# THB6064.net
KiCad netlist of a schematic drawn in EAGLE
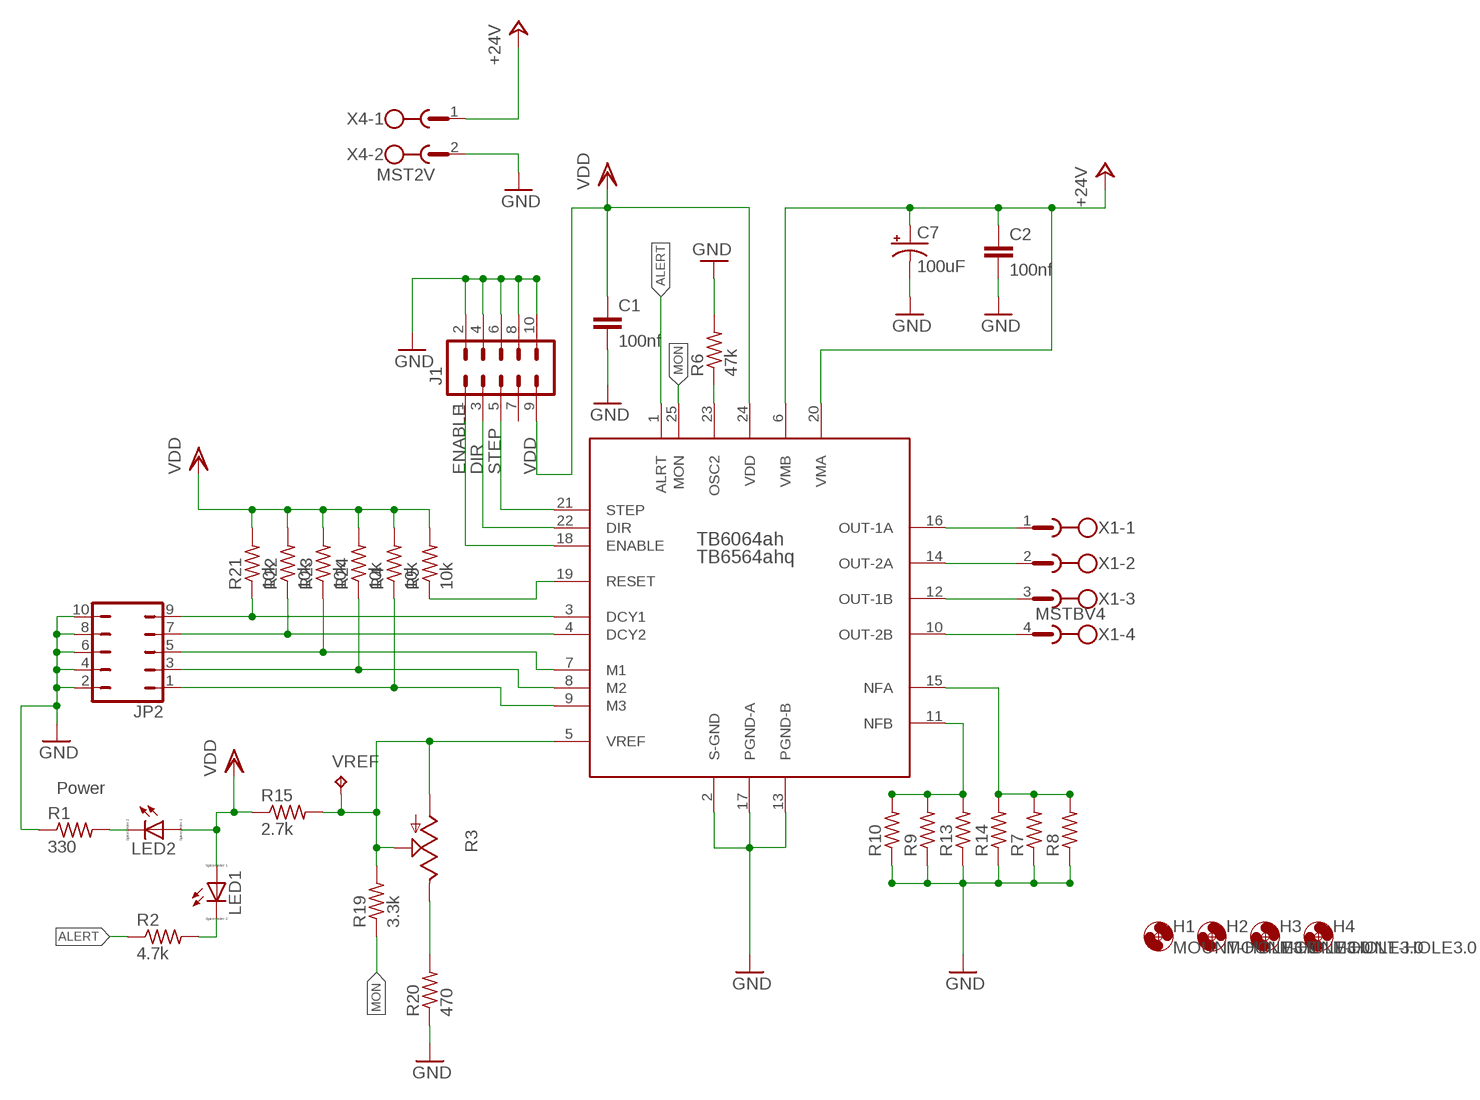
[diagram p0: schematic, sheet 1]

(export (version "E")
  (design (tool "Eeschema 10.0.6"))
  (components
    (comp (ref "C1")
      (value "100nf")
      (footprint "eagle-import:C1206")
      (libsource (lib "eagle-import") (part "C-EUC1206"))
    )
    (comp (ref "C2")
      (value "100nf")
      (footprint "eagle-import:C1206")
      (libsource (lib "eagle-import") (part "C-EUC1206"))
    )
    (comp (ref "C7")
      (value "100uF")
      (footprint "eagle-import:NIC_10X10.5_CAP")
      (libsource (lib "eagle-import") (part "100UF-63V-20%(ELECT)"))
    )
    (comp (ref "H1")
      (value "MOUNT-HOLE3.0")
      (footprint "eagle-import:3,0")
      (libsource (lib "eagle-import") (part "MOUNT-HOLE3.0"))
    )
    (comp (ref "H2")
      (value "MOUNT-HOLE3.0")
      (footprint "eagle-import:3,0")
      (libsource (lib "eagle-import") (part "MOUNT-HOLE3.0"))
    )
    (comp (ref "H3")
      (value "MOUNT-HOLE3.0")
      (footprint "eagle-import:3,0")
      (libsource (lib "eagle-import") (part "MOUNT-HOLE3.0"))
    )
    (comp (ref "H4")
      (value "MOUNT-HOLE3.0")
      (footprint "eagle-import:3,0")
      (libsource (lib "eagle-import") (part "MOUNT-HOLE3.0"))
    )
    (comp (ref "J1")
      (value "M05X2SHD")
      (footprint "eagle-import:2X5-SHROUDED")
      (libsource (lib "eagle-import") (part "M05X2SHD"))
    )
    (comp (ref "JP2")
      (value "JP5Q")
      (footprint "eagle-import:JP5Q")
      (libsource (lib "eagle-import") (part "JP5Q"))
    )
    (comp (ref "LED1")
      (value "LED_E")
      (footprint "eagle-import:LED_1206")
      (libsource (lib "eagle-import") (part "LED_E"))
    )
    (comp (ref "LED2")
      (value "LED_E")
      (footprint "eagle-import:LED_1206")
      (libsource (lib "eagle-import") (part "LED_E"))
    )
    (comp (ref "R1")
      (value "330")
      (footprint "eagle-import:R1206")
      (libsource (lib "eagle-import") (part "R-US_R1206"))
    )
    (comp (ref "R2")
      (value "4.7k")
      (footprint "eagle-import:R1206")
      (libsource (lib "eagle-import") (part "R-US_R1206"))
    )
    (comp (ref "R3")
      (value "TRIM_US-CA6V")
      (footprint "eagle-import:CA6V")
      (libsource (lib "eagle-import") (part "TRIM_US-CA6V"))
    )
    (comp (ref "R4")
      (value "10k")
      (footprint "eagle-import:R1206")
      (libsource (lib "eagle-import") (part "R-US_R1206"))
    )
    (comp (ref "R5")
      (value "10k")
      (footprint "eagle-import:R1206")
      (libsource (lib "eagle-import") (part "R-US_R1206"))
    )
    (comp (ref "R6")
      (value "47k")
      (footprint "eagle-import:R1206")
      (libsource (lib "eagle-import") (part "R-US_R1206"))
    )
    (comp (ref "R7")
      (value "R-US_R2512")
      (footprint "eagle-import:R2512")
      (libsource (lib "eagle-import") (part "R-US_R2512"))
    )
    (comp (ref "R8")
      (value "R-US_R2512")
      (footprint "eagle-import:R2512")
      (libsource (lib "eagle-import") (part "R-US_R2512"))
    )
    (comp (ref "R9")
      (value "R-US_R2512")
      (footprint "eagle-import:R2512")
      (libsource (lib "eagle-import") (part "R-US_R2512"))
    )
    (comp (ref "R10")
      (value "R-US_R2512")
      (footprint "eagle-import:R2512")
      (libsource (lib "eagle-import") (part "R-US_R2512"))
    )
    (comp (ref "R13")
      (value "R-US_R2512")
      (footprint "eagle-import:R2512")
      (libsource (lib "eagle-import") (part "R-US_R2512"))
    )
    (comp (ref "R14")
      (value "R-US_R2512")
      (footprint "eagle-import:R2512")
      (libsource (lib "eagle-import") (part "R-US_R2512"))
    )
    (comp (ref "R15")
      (value "2.7k")
      (footprint "eagle-import:R1206")
      (libsource (lib "eagle-import") (part "R-US_R1206"))
    )
    (comp (ref "R19")
      (value "3.3k")
      (footprint "eagle-import:R1206")
      (libsource (lib "eagle-import") (part "R-US_R1206"))
    )
    (comp (ref "R20")
      (value "470")
      (footprint "eagle-import:R1206")
      (libsource (lib "eagle-import") (part "R-US_R1206"))
    )
    (comp (ref "R21")
      (value "10k")
      (footprint "eagle-import:R1206")
      (libsource (lib "eagle-import") (part "R-US_R1206"))
    )
    (comp (ref "R22")
      (value "10k")
      (footprint "eagle-import:R1206")
      (libsource (lib "eagle-import") (part "R-US_R1206"))
    )
    (comp (ref "R23")
      (value "10k")
      (footprint "eagle-import:R1206")
      (libsource (lib "eagle-import") (part "R-US_R1206"))
    )
    (comp (ref "R24")
      (value "10k")
      (footprint "eagle-import:R1206")
      (libsource (lib "eagle-import") (part "R-US_R1206"))
    )
    (comp (ref "U$1")
      (value "THB6064")
      (footprint "eagle-import:ZIP25")
      (libsource (lib "eagle-import") (part "THB6064"))
    )
    (comp (ref "VREF")
      (value "TPPAD1-17")
      (footprint "eagle-import:P1-17")
      (libsource (lib "eagle-import") (part "TPPAD1-17"))
    )
    (comp (ref "X1")
      (value "MSTBV4")
      (footprint "eagle-import:MSTBV4")
      (fields (field (name "MPN") "MSTBV 2,5/4-GF-5.08"))
      (libsource (lib "eagle-import") (part "MSTBV4"))
    )
    (comp (ref "X4")
      (value "MST2V")
      (footprint "eagle-import:MSTBV2")
      (libsource (lib "eagle-import") (part "MST2V"))
    )
  )
  (nets
    (net (code "1") (name "+24V") (class "Default")
      (node (ref "C2") (pin "1") (pinfunction "1_1") (pintype "passive"))
      (node (ref "C7") (pin "+") (pinfunction "+_+") (pintype "passive"))
      (node (ref "U$1") (pin "20") (pinfunction "VMA_20") (pintype "bidirectional"))
      (node (ref "U$1") (pin "6") (pinfunction "VMB_6") (pintype "bidirectional"))
      (node (ref "X4") (pin "1") (pinfunction "1_1") (pintype "passive"))
    )
    (net (code "2") (name "/DIR") (class "Default")
      (node (ref "J1") (pin "3") (pinfunction "3_3") (pintype "passive"))
      (node (ref "U$1") (pin "22") (pinfunction "DIR_22") (pintype "bidirectional"))
    )
    (net (code "3") (name "/ENABLE") (class "Default")
      (node (ref "J1") (pin "1") (pinfunction "1_1") (pintype "passive"))
      (node (ref "U$1") (pin "18") (pinfunction "ENABLE_18") (pintype "bidirectional"))
    )
    (net (code "4") (name "/STEP") (class "Default")
      (node (ref "J1") (pin "5") (pinfunction "5_5") (pintype "passive"))
      (node (ref "U$1") (pin "21") (pinfunction "STEP_21") (pintype "bidirectional"))
    )
    (net (code "5") (name "ALERT") (class "Default")
      (node (ref "R2") (pin "1") (pinfunction "1_1") (pintype "passive"))
      (node (ref "U$1") (pin "1") (pinfunction "ALRT_1") (pintype "bidirectional"))
    )
    (net (code "6") (name "GND") (class "Default")
      (node (ref "C1") (pin "2") (pinfunction "2_2") (pintype "passive"))
      (node (ref "C2") (pin "2") (pinfunction "2_2") (pintype "passive"))
      (node (ref "C7") (pin "-") (pinfunction "-_-") (pintype "passive"))
      (node (ref "J1") (pin "10") (pinfunction "10_10") (pintype "passive"))
      (node (ref "J1") (pin "2") (pinfunction "2_2") (pintype "passive"))
      (node (ref "J1") (pin "4") (pinfunction "4_4") (pintype "passive"))
      (node (ref "J1") (pin "6") (pinfunction "6_6") (pintype "passive"))
      (node (ref "J1") (pin "8") (pinfunction "8_8") (pintype "passive"))
      (node (ref "JP2") (pin "10") (pinfunction "10_10") (pintype "passive"))
      (node (ref "JP2") (pin "2") (pinfunction "2_2") (pintype "passive"))
      (node (ref "JP2") (pin "4") (pinfunction "4_4") (pintype "passive"))
      (node (ref "JP2") (pin "6") (pinfunction "6_6") (pintype "passive"))
      (node (ref "JP2") (pin "8") (pinfunction "8_8") (pintype "passive"))
      (node (ref "R1") (pin "1") (pinfunction "1_1") (pintype "passive"))
      (node (ref "R10") (pin "1") (pinfunction "1_1") (pintype "passive"))
      (node (ref "R13") (pin "1") (pinfunction "1_1") (pintype "passive"))
      (node (ref "R14") (pin "1") (pinfunction "1_1") (pintype "passive"))
      (node (ref "R20") (pin "1") (pinfunction "1_1") (pintype "passive"))
      (node (ref "R6") (pin "2") (pinfunction "2_2") (pintype "passive"))
      (node (ref "R7") (pin "1") (pinfunction "1_1") (pintype "passive"))
      (node (ref "R8") (pin "1") (pinfunction "1_1") (pintype "passive"))
      (node (ref "R9") (pin "1") (pinfunction "1_1") (pintype "passive"))
      (node (ref "U$1") (pin "13") (pinfunction "PGND-B_13") (pintype "bidirectional"))
      (node (ref "U$1") (pin "17") (pinfunction "PGND-A_17") (pintype "bidirectional"))
      (node (ref "U$1") (pin "2") (pinfunction "S-GND_2") (pintype "bidirectional"))
      (node (ref "X4") (pin "2") (pinfunction "1_2") (pintype "passive"))
    )
    (net (code "7") (name "MON") (class "Default")
      (node (ref "R19") (pin "1") (pinfunction "1_1") (pintype "passive"))
      (node (ref "U$1") (pin "25") (pinfunction "MON_25") (pintype "bidirectional"))
    )
    (net (code "8") (name "Net-(LED1-PadC)") (class "Default")
      (node (ref "LED1") (pin "C") (pinfunction "C_C") (pintype "passive"))
      (node (ref "R2") (pin "2") (pinfunction "2_2") (pintype "passive"))
    )
    (net (code "9") (name "Net-(LED2-PadC)") (class "Default")
      (node (ref "LED2") (pin "C") (pinfunction "C_C") (pintype "passive"))
      (node (ref "R1") (pin "2") (pinfunction "2_2") (pintype "passive"))
    )
    (net (code "10") (name "Net-(R20-Pad2)") (class "Default")
      (node (ref "R20") (pin "2") (pinfunction "2_2") (pintype "passive"))
      (node (ref "R3") (pin "E") (pinfunction "E_E") (pintype "passive"))
    )
    (net (code "11") (name "Net-(U$1-DCY1)") (class "Default")
      (node (ref "JP2") (pin "9") (pinfunction "9_9") (pintype "passive"))
      (node (ref "R21") (pin "1") (pinfunction "1_1") (pintype "passive"))
      (node (ref "U$1") (pin "3") (pinfunction "DCY1_3") (pintype "bidirectional"))
    )
    (net (code "12") (name "Net-(U$1-DCY2)") (class "Default")
      (node (ref "JP2") (pin "7") (pinfunction "7_7") (pintype "passive"))
      (node (ref "R22") (pin "1") (pinfunction "1_1") (pintype "passive"))
      (node (ref "U$1") (pin "4") (pinfunction "DCY2_4") (pintype "bidirectional"))
    )
    (net (code "13") (name "Net-(U$1-M1)") (class "Default")
      (node (ref "JP2") (pin "5") (pinfunction "5_5") (pintype "passive"))
      (node (ref "R23") (pin "1") (pinfunction "1_1") (pintype "passive"))
      (node (ref "U$1") (pin "7") (pinfunction "M1_7") (pintype "bidirectional"))
    )
    (net (code "14") (name "Net-(U$1-M2)") (class "Default")
      (node (ref "JP2") (pin "3") (pinfunction "3_3") (pintype "passive"))
      (node (ref "R24") (pin "1") (pinfunction "1_1") (pintype "passive"))
      (node (ref "U$1") (pin "8") (pinfunction "M2_8") (pintype "bidirectional"))
    )
    (net (code "15") (name "Net-(U$1-M3)") (class "Default")
      (node (ref "JP2") (pin "1") (pinfunction "1_1") (pintype "passive"))
      (node (ref "R4") (pin "1") (pinfunction "1_1") (pintype "passive"))
      (node (ref "U$1") (pin "9") (pinfunction "M3_9") (pintype "bidirectional"))
    )
    (net (code "16") (name "Net-(U$1-NFA)") (class "Default")
      (node (ref "R14") (pin "2") (pinfunction "2_2") (pintype "passive"))
      (node (ref "R7") (pin "2") (pinfunction "2_2") (pintype "passive"))
      (node (ref "R8") (pin "2") (pinfunction "2_2") (pintype "passive"))
      (node (ref "U$1") (pin "15") (pinfunction "NFA_15") (pintype "bidirectional"))
    )
    (net (code "17") (name "Net-(U$1-NFB)") (class "Default")
      (node (ref "R10") (pin "2") (pinfunction "2_2") (pintype "passive"))
      (node (ref "R13") (pin "2") (pinfunction "2_2") (pintype "passive"))
      (node (ref "R9") (pin "2") (pinfunction "2_2") (pintype "passive"))
      (node (ref "U$1") (pin "11") (pinfunction "NFB_11") (pintype "bidirectional"))
    )
    (net (code "18") (name "Net-(U$1-OSC2)") (class "Default")
      (node (ref "R6") (pin "1") (pinfunction "1_1") (pintype "passive"))
      (node (ref "U$1") (pin "23") (pinfunction "OSC2_23") (pintype "bidirectional"))
    )
    (net (code "19") (name "Net-(U$1-OUT-1A)") (class "Default")
      (node (ref "U$1") (pin "16") (pinfunction "OUT-1A_16") (pintype "bidirectional"))
      (node (ref "X1") (pin "1") (pinfunction "1_1") (pintype "passive"))
    )
    (net (code "20") (name "Net-(U$1-OUT-1B)") (class "Default")
      (node (ref "U$1") (pin "12") (pinfunction "OUT-1B_12") (pintype "bidirectional"))
      (node (ref "X1") (pin "3") (pinfunction "1_3") (pintype "passive"))
    )
    (net (code "21") (name "Net-(U$1-OUT-2A)") (class "Default")
      (node (ref "U$1") (pin "14") (pinfunction "OUT-2A_14") (pintype "bidirectional"))
      (node (ref "X1") (pin "2") (pinfunction "1_2") (pintype "passive"))
    )
    (net (code "22") (name "Net-(U$1-OUT-2B)") (class "Default")
      (node (ref "U$1") (pin "10") (pinfunction "OUT-2B_10") (pintype "bidirectional"))
      (node (ref "X1") (pin "4") (pinfunction "1_4") (pintype "passive"))
    )
    (net (code "23") (name "Net-(U$1-RESET)") (class "Default")
      (node (ref "R5") (pin "1") (pinfunction "1_1") (pintype "passive"))
      (node (ref "U$1") (pin "19") (pinfunction "RESET_19") (pintype "bidirectional"))
    )
    (net (code "24") (name "Net-(U$1-VREF)") (class "Default")
      (node (ref "R15") (pin "2") (pinfunction "2_2") (pintype "passive"))
      (node (ref "R19") (pin "2") (pinfunction "2_2") (pintype "passive"))
      (node (ref "R3") (pin "A") (pinfunction "A_A") (pintype "passive"))
      (node (ref "R3") (pin "S") (pinfunction "S_S") (pintype "passive"))
      (node (ref "U$1") (pin "5") (pinfunction "VREF_5") (pintype "bidirectional"))
      (node (ref "VREF") (pin "TP") (pinfunction "TP_TP") (pintype "input"))
    )
    (net (code "25") (name "VDD") (class "Default")
      (node (ref "C1") (pin "1") (pinfunction "1_1") (pintype "passive"))
      (node (ref "J1") (pin "9") (pinfunction "9_9") (pintype "passive"))
      (node (ref "LED1") (pin "A") (pinfunction "A_A") (pintype "passive"))
      (node (ref "LED2") (pin "A") (pinfunction "A_A") (pintype "passive"))
      (node (ref "R15") (pin "1") (pinfunction "1_1") (pintype "passive"))
      (node (ref "R21") (pin "2") (pinfunction "2_2") (pintype "passive"))
      (node (ref "R22") (pin "2") (pinfunction "2_2") (pintype "passive"))
      (node (ref "R23") (pin "2") (pinfunction "2_2") (pintype "passive"))
      (node (ref "R24") (pin "2") (pinfunction "2_2") (pintype "passive"))
      (node (ref "R4") (pin "2") (pinfunction "2_2") (pintype "passive"))
      (node (ref "R5") (pin "2") (pinfunction "2_2") (pintype "passive"))
      (node (ref "U$1") (pin "24") (pinfunction "VDD_24") (pintype "bidirectional"))
    )
    (net (code "26") (name "unconnected-(J1-Pad7)") (class "Default")
      (node (ref "J1") (pin "7") (pinfunction "7_7") (pintype "passive"))
    )
  )
)
